# Sheet.net
KiCad netlist of a schematic drawn in Altium Designer
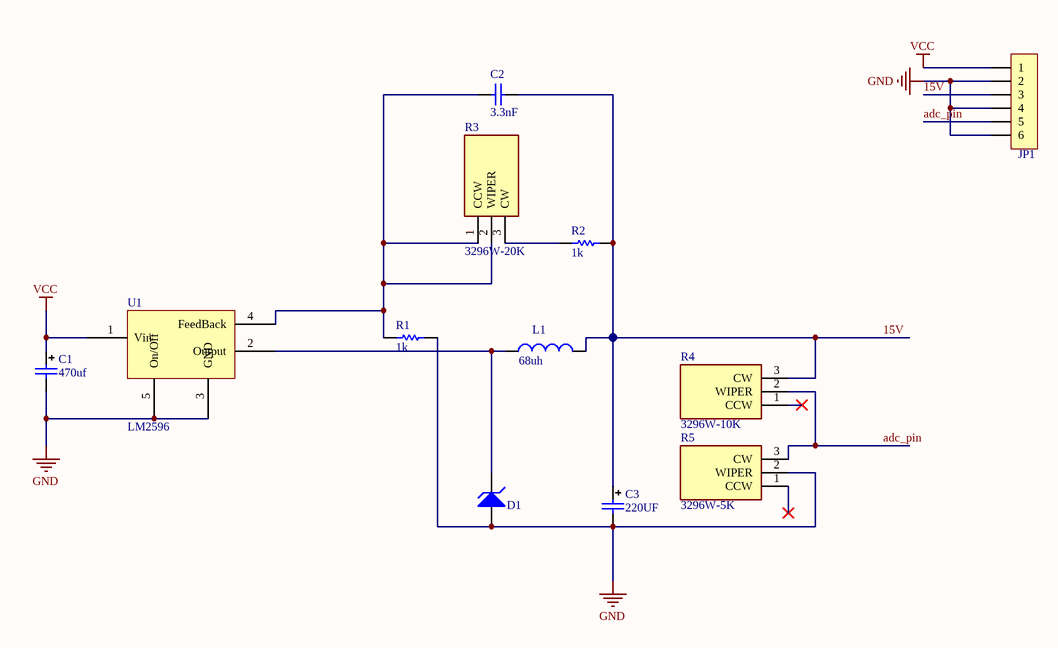
[diagram p0: Sheet.SchDoc]

(export (version "E")
  (design (tool "Eeschema 10.0.6"))
  (components
    (comp (ref "C1")
      (value "470uf")
      (footprint "CAP 5.0*10*16")
      (description "CAP_DIP")
      (libsource (lib "生仪科协V5.3") (part "CAP_DIP"))
    )
    (comp (ref "C2")
      (value "3.3nF")
      (footprint "C0805")
      (description "CAP_0805")
      (fields
        (field (name "MANUFACTURER") "Generic Components")
        (field (name "PUBLISHER") "Altium Hobart Technology Centre")
      )
      (libsource (lib "生仪科协V5.3") (part "CAP_0805"))
    )
    (comp (ref "C3")
      (value "220UF")
      (footprint "CAP 5.0*10*16")
      (description "CAP_DIP")
      (libsource (lib "生仪科协V5.3") (part "CAP_DIP"))
    )
    (comp (ref "D1")
      (value "Diode  Zener")
      (footprint "SMC")
      (description "Zener Diode")
      (fields (field (name "PUBLISHER") "Altium Limited"))
      (libsource (lib "LisieLib_Ultimate v6.0") (part "Diode  Zener"))
    )
    (comp (ref "JP1")
      (value "HDR-1X6")
      (footprint "KF128-3.81-6P")
      (description "6P接插件")
      (fields (field (name "版权归属") "源创客"))
      (libsource (lib "4.2   - 接插件-脚距1.25") (part "Header 6"))
    )
    (comp (ref "L1")
      (value "68uh")
      (footprint "CDRH74")
      (description "电感")
      (fields (field (name "PUBLISHER") "Altium Limited"))
      (libsource (lib "LisieLib_Ultimate v6.0") (part "INDUCTOR"))
    )
    (comp (ref "R1")
      (value "1k")
      (footprint "6-0805_M")
      (description "0805电阻")
      (fields
        (field (name "MANUFACTURER") "Generic Components")
        (field (name "PUBLISHER") "Altium Hobart Technology Centre")
      )
      (libsource (lib "生仪科协V5.3") (part "Res"))
    )
    (comp (ref "R2")
      (value "1k")
      (footprint "6-0805_M")
      (description "0805电阻")
      (fields
        (field (name "MANUFACTURER") "Generic Components")
        (field (name "PUBLISHER") "Altium Hobart Technology Centre")
      )
      (libsource (lib "生仪科协V5.3") (part "Res"))
    )
    (comp (ref "R3")
      (value "3296W-20K")
      (footprint "SamacSys:3296W-1")
      (description "Resistor")
      (fields
        (field (name "MANUFACTURER_PART_NUMBER") "3296W-1-100LF")
        (field (name "MOUSER PART NUMBER") "652-3296W-1-100LF")
      )
      (libsource (lib "") (part "3296W-1-100LF_1"))
    )
    (comp (ref "R4")
      (value "3296W-10K")
      (footprint "SamacSys:3296W-1")
      (description "Resistor")
      (fields
        (field (name "MANUFACTURER_PART_NUMBER") "3296W-1-100LF")
        (field (name "MOUSER PART NUMBER") "652-3296W-1-100LF")
      )
      (libsource (lib "*") (part "3296W-1-100LF"))
    )
    (comp (ref "R5")
      (value "3296W-5K")
      (footprint "SamacSys:3296W-1")
      (description "Resistor")
      (fields
        (field (name "MANUFACTURER_PART_NUMBER") "3296W-1-100LF")
        (field (name "MOUSER PART NUMBER") "652-3296W-1-100LF")
      )
      (libsource (lib "*") (part "3296W-1-100LF"))
    )
    (comp (ref "U1") (value "LM2596") (footprint "TO263-5A") (libsource (lib "王姗姗SCHLib") (part "LM2596")))
  )
  (nets
    (net (code "1") (name "/15V") (class "Default")
      (node (ref "C2") (pin "2") (pinfunction "2_2") (pintype "passive"))
      (node (ref "C3") (pin "1") (pinfunction "1_1") (pintype "passive"))
      (node (ref "JP1") (pin "3") (pinfunction "3_3") (pintype "passive"))
      (node (ref "L1") (pin "2") (pinfunction "2_2") (pintype "passive"))
      (node (ref "R2") (pin "2") (pinfunction "2_2") (pintype "passive"))
      (node (ref "R4") (pin "3") (pinfunction "CW_3") (pintype "passive"))
    )
    (net (code "2") (name "/adc_pin") (class "Default")
      (node (ref "JP1") (pin "5") (pinfunction "5_5") (pintype "passive"))
      (node (ref "R4") (pin "2") (pinfunction "WIPER_2") (pintype "passive"))
      (node (ref "R5") (pin "3") (pinfunction "CW_3") (pintype "passive"))
    )
    (net (code "3") (name "GND") (class "Default")
      (node (ref "C1") (pin "2") (pinfunction "2_2") (pintype "passive"))
      (node (ref "C3") (pin "2") (pinfunction "2_2") (pintype "passive"))
      (node (ref "D1") (pin "1") (pinfunction "A_1") (pintype "passive"))
      (node (ref "JP1") (pin "2") (pinfunction "2_2") (pintype "passive"))
      (node (ref "JP1") (pin "4") (pinfunction "4_4") (pintype "passive"))
      (node (ref "JP1") (pin "6") (pinfunction "6_6") (pintype "passive"))
      (node (ref "R1") (pin "1") (pinfunction "1_1") (pintype "passive"))
      (node (ref "R5") (pin "2") (pinfunction "WIPER_2") (pintype "passive"))
      (node (ref "U1") (pin "3") (pinfunction "GND_3") (pintype "passive"))
      (node (ref "U1") (pin "5") (pinfunction "On/Off_5") (pintype "passive"))
    )
    (net (code "4") (name "Net-(D1-K)") (class "Default")
      (node (ref "D1") (pin "2") (pinfunction "K_2") (pintype "passive"))
      (node (ref "L1") (pin "1") (pinfunction "1_1") (pintype "passive"))
      (node (ref "U1") (pin "2") (pinfunction "Output_2") (pintype "passive"))
    )
    (net (code "5") (name "Net-(R3-CCW)") (class "Default")
      (node (ref "C2") (pin "1") (pinfunction "1_1") (pintype "passive"))
      (node (ref "R1") (pin "2") (pinfunction "2_2") (pintype "passive"))
      (node (ref "R3") (pin "1") (pinfunction "CCW_1") (pintype "passive"))
      (node (ref "R3") (pin "2") (pinfunction "WIPER_2") (pintype "passive"))
      (node (ref "U1") (pin "4") (pinfunction "FeedBack_4") (pintype "passive"))
    )
    (net (code "6") (name "Net-(R3-CW)") (class "Default")
      (node (ref "R2") (pin "1") (pinfunction "1_1") (pintype "passive"))
      (node (ref "R3") (pin "3") (pinfunction "CW_3") (pintype "passive"))
    )
    (net (code "7") (name "VCC") (class "Default")
      (node (ref "C1") (pin "1") (pinfunction "1_1") (pintype "passive"))
      (node (ref "JP1") (pin "1") (pinfunction "1_1") (pintype "passive"))
      (node (ref "U1") (pin "1") (pinfunction "Vin_1") (pintype "passive"))
    )
    (net (code "8") (name "unconnected-(R4-CCW-Pad1)") (class "Default")
      (node (ref "R4") (pin "1") (pinfunction "CCW_1") (pintype "passive+no_connect"))
    )
    (net (code "9") (name "unconnected-(R5-CCW-Pad1)") (class "Default")
      (node (ref "R5") (pin "1") (pinfunction "CCW_1") (pintype "passive+no_connect"))
    )
  )
)
